# BLDCSuperBot.net
KiCad netlist of a schematic drawn in Altium Designer
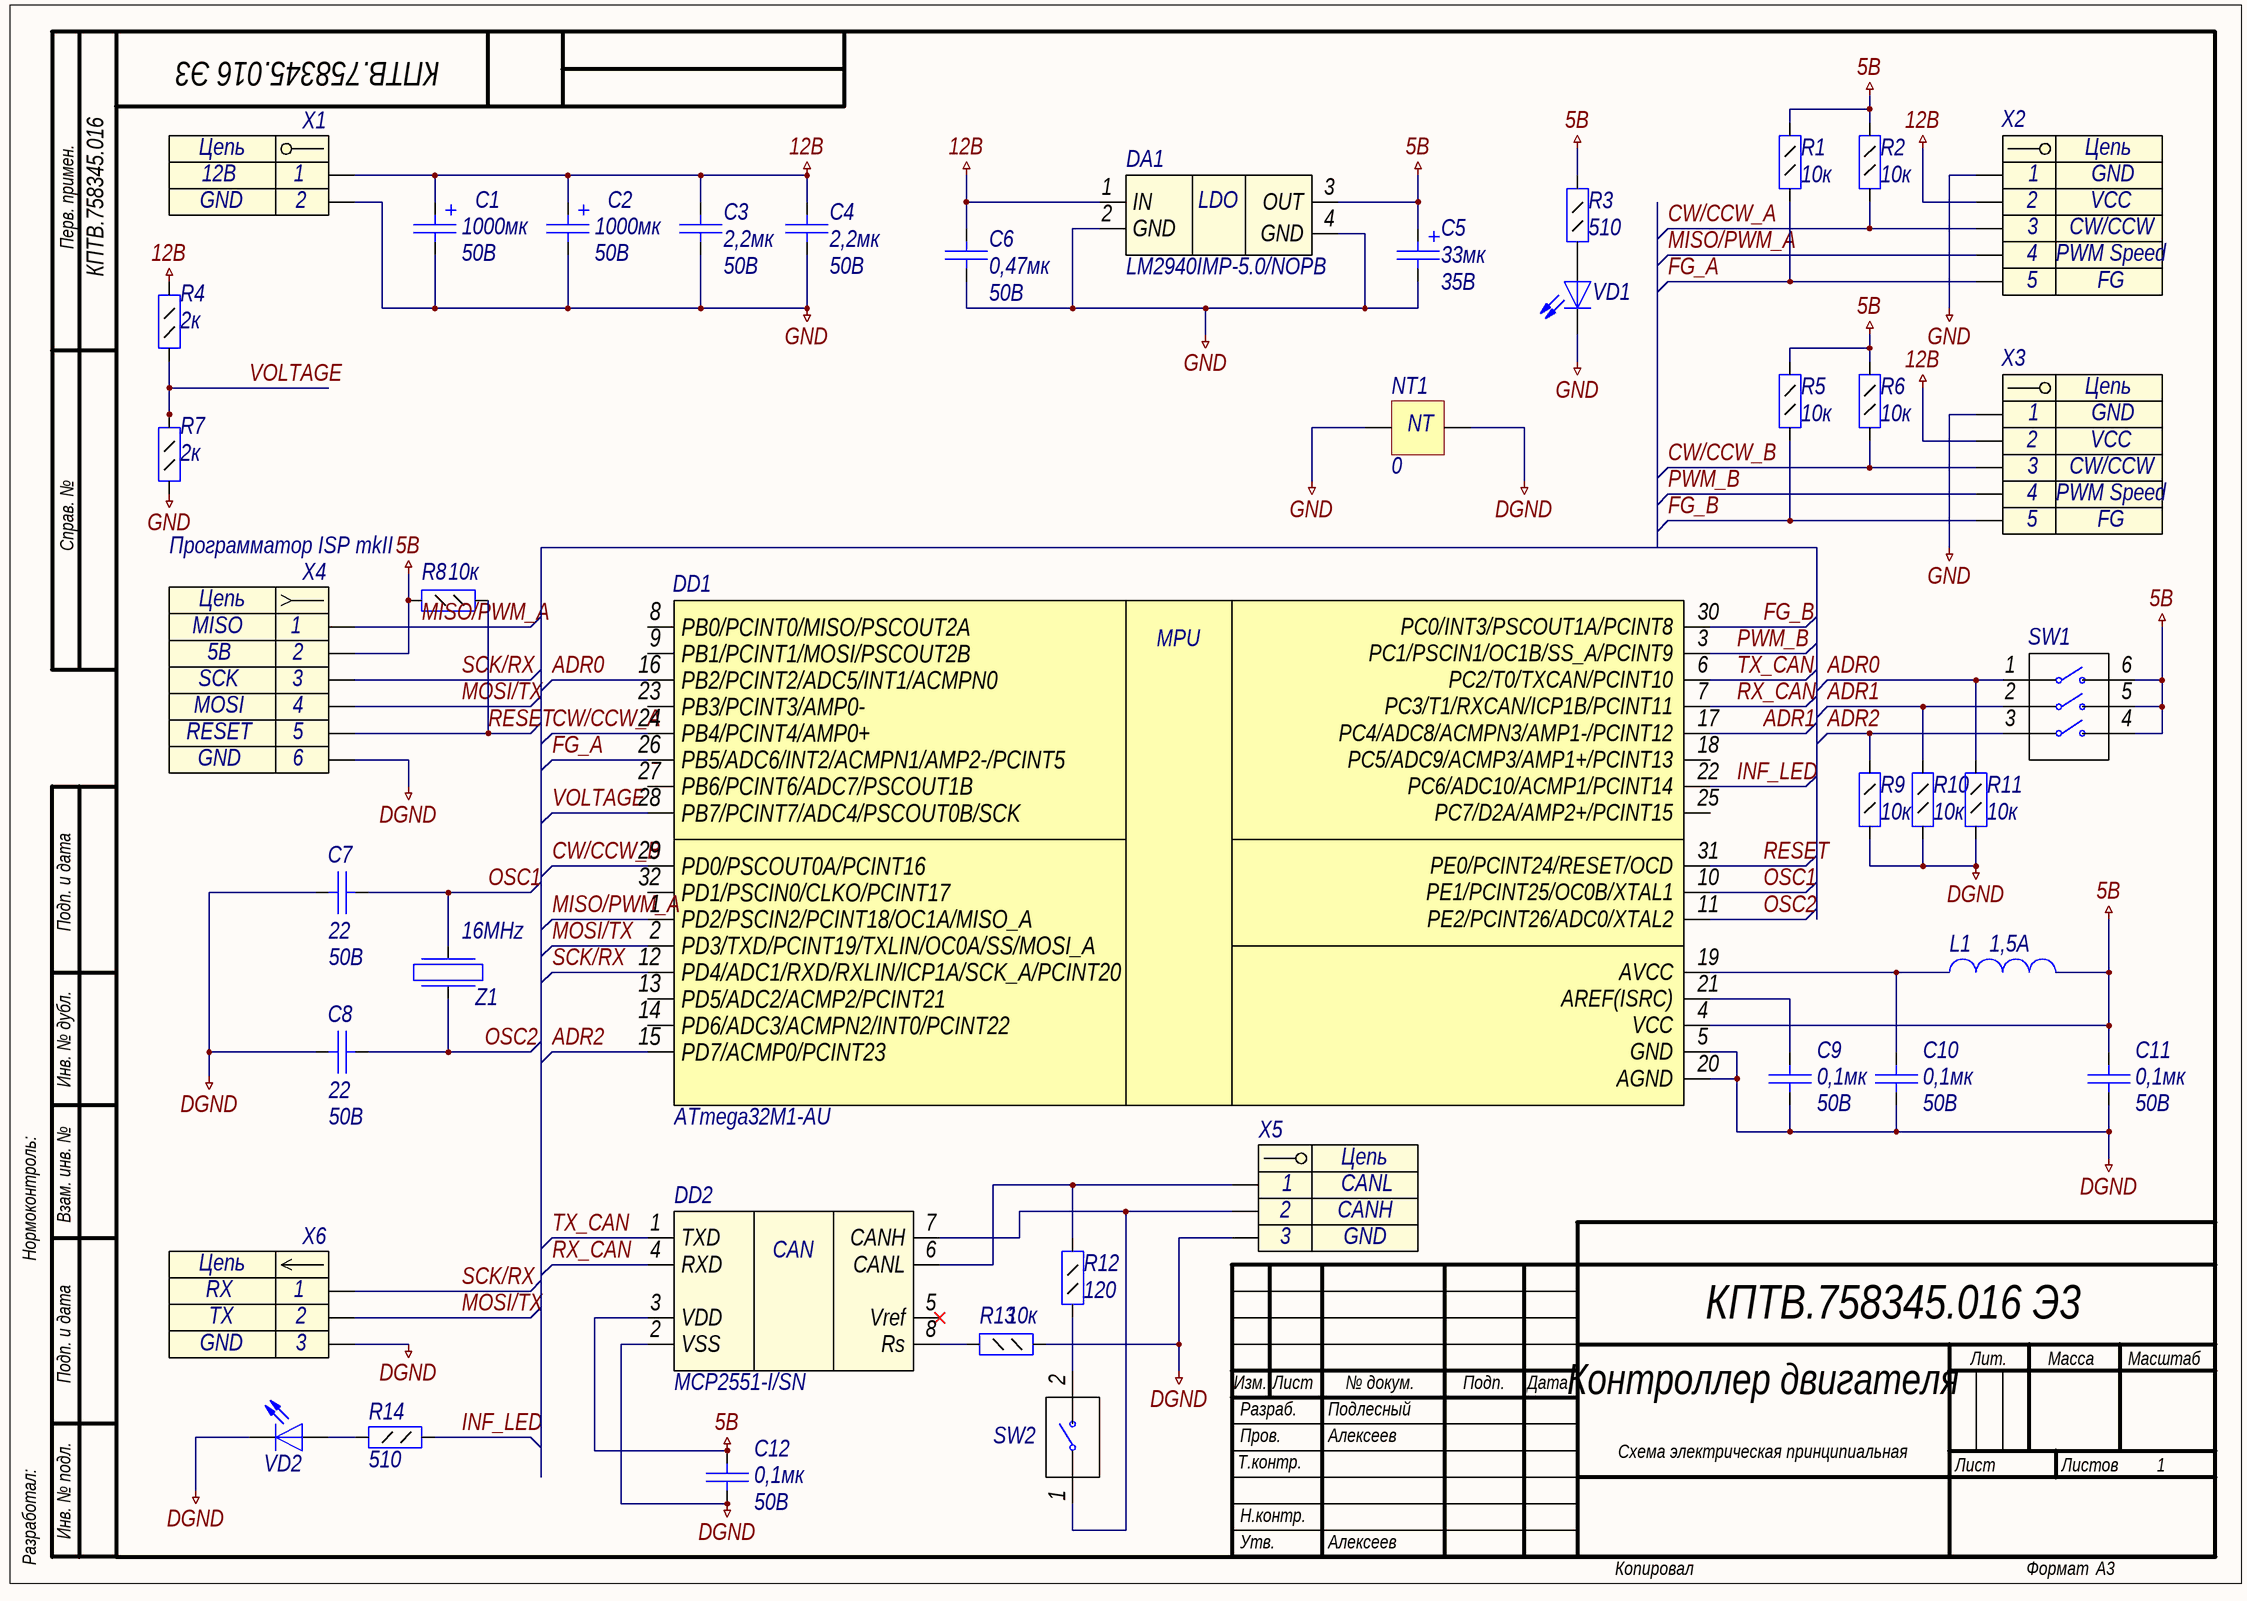
[diagram p0: BLDCSuperBot.schdoc]

(export (version "E")
  (design (tool "Eeschema 10.0.6"))
  (components
    (comp (ref "C1")
      (value "1000мк")
      (footprint "K50-35(13X25)_V")
      (description "Конденсатор полярный")
      (fields
        (field (name "VOLTAGE") "50В")
        (field (name "PART NUMBER") "TKR102M1HJ21")
        (field (name "Comment") "Capacitor_pol")
      )
      (libsource (lib "MOP44") (part "Capacitor_pol"))
    )
    (comp (ref "C2")
      (value "1000мк")
      (footprint "K50-35(13X25)_V")
      (description "Конденсатор полярный")
      (fields
        (field (name "VOLTAGE") "50В")
        (field (name "PART NUMBER") "TKR102M1HJ21")
        (field (name "Comment") "Capacitor_pol")
      )
      (libsource (lib "MOP44") (part "Capacitor_pol"))
    )
    (comp (ref "C3")
      (value "2,2мк")
      (footprint "C1206")
      (description "Конденсатор")
      (fields
        (field (name "VOLTAGE") "50В")
        (field (name "PART NUMBER") "GRM31CR71H225KA88**L")
        (field (name "Comment") "Capacitor")
      )
      (libsource (lib "MOP44") (part "Capacitor"))
    )
    (comp (ref "C4")
      (value "2,2мк")
      (footprint "C1206")
      (description "Конденсатор")
      (fields
        (field (name "VOLTAGE") "50В")
        (field (name "PART NUMBER") "GRM31CR71H225KA88**L")
        (field (name "Comment") "Capacitor")
      )
      (libsource (lib "MOP44") (part "Capacitor"))
    )
    (comp (ref "C5")
      (value "33мк")
      (footprint "TANTAL CASE D")
      (description "Конденсатор полярный")
      (fields
        (field (name "VOLTAGE") "35В")
        (field (name "PART NUMBER") "TAJD336K035RNJ")
        (field (name "Comment") "Capacitor_pol")
      )
      (libsource (lib "MOP44") (part "Capacitor_pol"))
    )
    (comp (ref "C6")
      (value "0,47мк")
      (footprint "C0805")
      (description "Конденсатор")
      (fields
        (field (name "VOLTAGE") "50B")
        (field (name "PART NUMBER") "GRM219R71C474K")
        (field (name "Comment") "Capacitor")
      )
      (libsource (lib "MOP44") (part "Capacitor"))
    )
    (comp (ref "C7")
      (value "22")
      (footprint "C0805")
      (description "Конденсатор")
      (fields
        (field (name "VOLTAGE") "50В")
        (field (name "PART NUMBER") "GRM21A5C2E220JW01D")
        (field (name "Comment") "Capacitor")
      )
      (libsource (lib "MOP44") (part "Capacitor"))
    )
    (comp (ref "C8")
      (value "22")
      (footprint "C0805")
      (description "Конденсатор")
      (fields
        (field (name "VOLTAGE") "50В")
        (field (name "PART NUMBER") "GRM21A5C2E220JW01D")
        (field (name "Comment") "Capacitor")
      )
      (libsource (lib "MOP44") (part "Capacitor"))
    )
    (comp (ref "C9")
      (value "0,1мк")
      (footprint "C0805")
      (description "Конденсатор")
      (fields
        (field (name "VOLTAGE") "50В")
        (field (name "PART NUMBER") "GRM21BR71H104KA01L ")
        (field (name "Comment") "Capacitor")
      )
      (libsource (lib "MOP44") (part "Capacitor"))
    )
    (comp (ref "C10")
      (value "0,1мк")
      (footprint "C0805")
      (description "Конденсатор")
      (fields
        (field (name "VOLTAGE") "50В")
        (field (name "PART NUMBER") "GRM21BR71H104KA01L ")
        (field (name "Comment") "Capacitor")
      )
      (libsource (lib "MOP44") (part "Capacitor"))
    )
    (comp (ref "C11")
      (value "0,1мк")
      (footprint "C0805")
      (description "Конденсатор")
      (fields
        (field (name "VOLTAGE") "50В")
        (field (name "PART NUMBER") "GRM21BR71H104KA01L ")
        (field (name "Comment") "Capacitor")
      )
      (libsource (lib "MOP44") (part "Capacitor"))
    )
    (comp (ref "C12")
      (value "0,1мк")
      (footprint "C0805")
      (description "Конденсатор")
      (fields
        (field (name "VOLTAGE") "50В")
        (field (name "PART NUMBER") "GRM21BR71H104KA01L ")
        (field (name "Comment") "Capacitor")
      )
      (libsource (lib "MOP44") (part "Capacitor"))
    )
    (comp (ref "DA1")
      (value "LM2940IMP")
      (footprint "SOT-223")
      (description "Low-Dropout Regulator for 5-V to 3.3-V Conversion")
      (fields
        (field (name "PART NUMBER") "LM2940IMP-5.0/NOPB")
        (field (name "MANUFACTURER") "Texas Instruments")
      )
      (libsource (lib "MOP44") (part "LM2940IMP"))
    )
    (comp (ref "DD1")
      (value "ATmega32M1-AU")
      (footprint "TQFP-32")
      (description "Микроконтроллер 8-Бит, AVR, 16МГц, 32КБ Flash")
      (libsource (lib "MOP44") (part "ATmega32M1-AU"))
    )
    (comp (ref "DD2")
      (value "MCP2551-I/SN")
      (footprint "SO8")
      (description "High-Speed CAN Transceiver")
      (libsource (lib "MOP44") (part "MCP2551-I/SN"))
    )
    (comp (ref "L1")
      (value "Inductor")
      (footprint "L0603")
      (description "EMI Suppression Filter")
      (fields (field (name "RATED CURRENT") "1,5A") (field (name "PART NUMBER") "BLM18PG181SN1D"))
      (libsource (lib "MOP44") (part "Inductor"))
    )
    (comp (ref "NT1") (value "0") (footprint "Pofigistor0603") (libsource (lib "MOP44") (part "Pofigistor")))
    (comp (ref "R1")
      (value "10к")
      (footprint "R0805")
      (description "Резистор")
      (fields (field (name "POWER") "0,125Вт") (field (name "Comment") "Resistor_0,125Вт"))
      (libsource (lib "") (part "Resistor_0,125Вт_1"))
    )
    (comp (ref "R2")
      (value "10к")
      (footprint "R0805")
      (description "Резистор")
      (fields (field (name "POWER") "0,125Вт") (field (name "Comment") "Resistor_0,125Вт"))
      (libsource (lib "") (part "Resistor_0,125Вт_1"))
    )
    (comp (ref "R3")
      (value "510")
      (footprint "R0805")
      (description "Резистор")
      (fields (field (name "PART NUMBER") "RC0805FR-07510RL") (field (name "POWER") "0,125Вт"))
      (libsource (lib "") (part "Resistor_0,125Вт_2"))
    )
    (comp (ref "R4")
      (value "2к")
      (footprint "R0805")
      (description "Резистор")
      (fields (field (name "PART NUMBER") "RC0805FR-072KL") (field (name "POWER") "0,125Вт"))
      (libsource (lib "") (part "Resistor_0,125Вт_2"))
    )
    (comp (ref "R5")
      (value "10к")
      (footprint "R0805")
      (description "Резистор")
      (fields (field (name "POWER") "0,125Вт") (field (name "Comment") "Resistor_0,125Вт"))
      (libsource (lib "") (part "Resistor_0,125Вт_1"))
    )
    (comp (ref "R6")
      (value "10к")
      (footprint "R0805")
      (description "Резистор")
      (fields (field (name "POWER") "0,125Вт") (field (name "Comment") "Resistor_0,125Вт"))
      (libsource (lib "") (part "Resistor_0,125Вт_1"))
    )
    (comp (ref "R7")
      (value "2к")
      (footprint "R0805")
      (description "Резистор")
      (fields (field (name "PART NUMBER") "RC0805FR-072KL") (field (name "POWER") "0,125Вт"))
      (libsource (lib "") (part "Resistor_0,125Вт_2"))
    )
    (comp (ref "R8")
      (value "10к")
      (footprint "R0805")
      (description "Резистор")
      (fields (field (name "POWER") "0,125Вт") (field (name "Comment") "Resistor_0,125Вт"))
      (libsource (lib "MOP44") (part "Resistor_0,125Вт"))
    )
    (comp (ref "R9")
      (value "10к")
      (footprint "R0805")
      (description "Резистор")
      (fields (field (name "POWER") "0,125Вт") (field (name "Comment") "Resistor_0,125Вт"))
      (libsource (lib "") (part "Resistor_0,125Вт_1"))
    )
    (comp (ref "R10")
      (value "10к")
      (footprint "R0805")
      (description "Резистор")
      (fields (field (name "POWER") "0,125Вт") (field (name "Comment") "Resistor_0,125Вт"))
      (libsource (lib "") (part "Resistor_0,125Вт_1"))
    )
    (comp (ref "R11")
      (value "10к")
      (footprint "R0805")
      (description "Резистор")
      (fields (field (name "POWER") "0,125Вт") (field (name "Comment") "Resistor_0,125Вт"))
      (libsource (lib "") (part "Resistor_0,125Вт_1"))
    )
    (comp (ref "R12")
      (value "120")
      (footprint "R0805")
      (description "Резистор")
      (fields (field (name "PART NUMBER") "RC0805FR-07120RL") (field (name "POWER") "0,125Вт"))
      (libsource (lib "") (part "Resistor_0,125Вт_2"))
    )
    (comp (ref "R13")
      (value "10к")
      (footprint "R0805")
      (description "Резистор")
      (fields (field (name "POWER") "0,125Вт") (field (name "Comment") "Resistor_0,125Вт"))
      (libsource (lib "MOP44") (part "Resistor_0,125Вт"))
    )
    (comp (ref "R14")
      (value "510")
      (footprint "R0805")
      (description "Резистор")
      (fields (field (name "PART NUMBER") "RC0805FR-07510RL") (field (name "POWER") "0,125Вт"))
      (libsource (lib "") (part "Resistor_0,125Вт_1"))
    )
    (comp (ref "SW1")
      (value "~")
      (footprint "DIP3")
      (description "DIP переключатель адреса")
      (fields (field (name "PART NUMBER") "DS1040-03RN"))
      (libsource (lib "MOP44") (part "DS1040-03"))
    )
    (comp (ref "SW2")
      (value "DS1040-01")
      (footprint "DIP1")
      (description "DIP переключатель")
      (fields (field (name "PART NUMBER") "DS1040-01RN"))
      (libsource (lib "MOP44") (part "DS1040-01"))
    )
    (comp (ref "VD1")
      (value "LED")
      (footprint "L_0805")
      (description "Светодиод")
      (fields (field (name "PART NUMBER") "KP-2012EC"))
      (libsource (lib "MOP44") (part "LED"))
    )
    (comp (ref "VD2")
      (value "LED")
      (footprint "L_0805")
      (description "Светодиод")
      (fields (field (name "PART NUMBER") "KP-2012EC"))
      (libsource (lib "MOP44") (part "LED"))
    )
    (comp (ref "X1")
      (value "Header_2_trm")
      (footprint "TERMINAL-2WAY-5MM")
      (description "Разъем - 2 конт. клеммник")
      (libsource (lib "MOP44") (part "Header_2_trm"))
    )
    (comp (ref "X2")
      (value "Header_5_trm")
      (footprint "TERMINAL-5WAY-3.5MM_")
      (description "Разъем - 5 конт. клеммник")
      (libsource (lib "MOP44") (part "Header_5_trm"))
    )
    (comp (ref "X3")
      (value "Header_5_trm")
      (footprint "TERMINAL-5WAY-3.5MM")
      (description "Разъем - 5 конт. клеммник")
      (libsource (lib "MOP44") (part "Header_5_trm"))
    )
    (comp (ref "X4")
      (value "Программатор ISP mkII")
      (footprint "PLS2-6")
      (description "Разъем - 6 конт. розетка")
      (libsource (lib "MOP44") (part "Header_6_sct"))
    )
    (comp (ref "X5")
      (value "Header_3_trm")
      (footprint "TERMINAL-3WAY-3.5MM")
      (description "Разъем - 3 конт. клеммник")
      (libsource (lib "MOP44") (part "Header_3_trm"))
    )
    (comp (ref "X6")
      (value "Header_3_plg")
      (footprint "PLS-3")
      (description "Разъем - 3 конт. вилка")
      (fields (field (name "PART NUMBER") "DS1021-1*3SF112-B"))
      (libsource (lib "MOP44") (part "Header_3_plg"))
    )
    (comp (ref "Z1")
      (value "Crystal")
      (footprint "HC-49S")
      (description "Кварцевый резонатор")
      (fields (field (name "FREQUENCE") "16MHz") (field (name "PART NUMBER") "16.000MHzHC-49US"))
      (libsource (lib "MOP44") (part "Crystal"))
    )
  )
  (nets
    (net (code "1") (name "/ADR0") (class "Default")
      (node (ref "DD1") (pin "16") (pinfunction "PB2/PCINT2/ADC5/INT1/ACMPN0_16") (pintype "passive"))
      (node (ref "R11") (pin "1") (pinfunction "1_1") (pintype "passive"))
      (node (ref "SW1") (pin "1") (pintype "passive"))
    )
    (net (code "2") (name "/ADR1") (class "Default")
      (node (ref "DD1") (pin "17") (pinfunction "PC4/ADC8/ACMPN3/AMP1-/PCINT12_17") (pintype "passive"))
      (node (ref "R10") (pin "1") (pinfunction "1_1") (pintype "passive"))
      (node (ref "SW1") (pin "2") (pintype "passive"))
    )
    (net (code "3") (name "/ADR2") (class "Default")
      (node (ref "DD1") (pin "15") (pinfunction "PD7/ACMP0/PCINT23_15") (pintype "passive"))
      (node (ref "R9") (pin "1") (pinfunction "1_1") (pintype "passive"))
      (node (ref "SW1") (pin "3") (pintype "passive"))
    )
    (net (code "4") (name "/CW{slash}CCW_A") (class "Default")
      (node (ref "DD1") (pin "24") (pinfunction "PB4/PCINT4/AMP0+_24") (pintype "passive"))
      (node (ref "R2") (pin "2") (pinfunction "2_2") (pintype "passive"))
      (node (ref "X2") (pin "3") (pinfunction "3_3") (pintype "passive"))
    )
    (net (code "5") (name "/CW{slash}CCW_B") (class "Default")
      (node (ref "DD1") (pin "29") (pinfunction "PD0/PSCOUT0A/PCINT16_29") (pintype "passive"))
      (node (ref "R6") (pin "2") (pinfunction "2_2") (pintype "passive"))
      (node (ref "X3") (pin "3") (pinfunction "3_3") (pintype "passive"))
    )
    (net (code "6") (name "/FG_A") (class "Default")
      (node (ref "DD1") (pin "26") (pinfunction "PB5/ADC6/INT2/ACMPN1/AMP2-/PCINT5_26") (pintype "passive"))
      (node (ref "R1") (pin "2") (pinfunction "2_2") (pintype "passive"))
      (node (ref "X2") (pin "5") (pinfunction "5_5") (pintype "passive"))
    )
    (net (code "7") (name "/FG_B") (class "Default")
      (node (ref "DD1") (pin "30") (pinfunction "PC0/INT3/PSCOUT1A/PCINT8_30") (pintype "passive"))
      (node (ref "R5") (pin "2") (pinfunction "2_2") (pintype "passive"))
      (node (ref "X3") (pin "5") (pinfunction "5_5") (pintype "passive"))
    )
    (net (code "8") (name "/INF_LED") (class "Default")
      (node (ref "DD1") (pin "22") (pinfunction "PC6/ADC10/ACMP1/PCINT14_22") (pintype "passive"))
      (node (ref "R14") (pin "1") (pinfunction "1_1") (pintype "passive"))
    )
    (net (code "9") (name "/MISO{slash}PWM_A") (class "Default")
      (node (ref "DD1") (pin "1") (pinfunction "PD2/PSCIN2/PCINT18/OC1A/MISO_A_1") (pintype "passive"))
      (node (ref "X2") (pin "4") (pinfunction "4_4") (pintype "passive"))
      (node (ref "X4") (pin "1") (pinfunction "1_1") (pintype "passive"))
    )
    (net (code "10") (name "/MOSI{slash}TX") (class "Default")
      (node (ref "DD1") (pin "2") (pinfunction "PD3/TXD/PCINT19/TXLIN/OC0A/SS/MOSI_A_2") (pintype "passive"))
      (node (ref "X4") (pin "4") (pinfunction "4_4") (pintype "passive"))
      (node (ref "X6") (pin "2") (pinfunction "2_2") (pintype "passive"))
    )
    (net (code "11") (name "/OSC1") (class "Default")
      (node (ref "C7") (pin "1") (pinfunction "1_1") (pintype "passive"))
      (node (ref "DD1") (pin "10") (pinfunction "PE1/PCINT25/OC0B/XTAL1_10") (pintype "passive"))
      (node (ref "Z1") (pin "2") (pinfunction "2_2") (pintype "passive"))
    )
    (net (code "12") (name "/OSC2") (class "Default")
      (node (ref "C8") (pin "1") (pinfunction "1_1") (pintype "passive"))
      (node (ref "DD1") (pin "11") (pinfunction "PE2/PCINT26/ADC0/XTAL2_11") (pintype "passive"))
      (node (ref "Z1") (pin "1") (pinfunction "1_1") (pintype "passive"))
    )
    (net (code "13") (name "/PWM_B") (class "Default")
      (node (ref "DD1") (pin "3") (pinfunction "PC1/PSCIN1/OC1B/SS_A/PCINT9_3") (pintype "passive"))
      (node (ref "X3") (pin "4") (pinfunction "4_4") (pintype "passive"))
    )
    (net (code "14") (name "/RESET") (class "Default")
      (node (ref "DD1") (pin "31") (pinfunction "PE0/PCINT24/RESET/OCD_31") (pintype "passive"))
      (node (ref "R8") (pin "1") (pinfunction "1_1") (pintype "passive"))
      (node (ref "X4") (pin "5") (pinfunction "5_5") (pintype "passive"))
    )
    (net (code "15") (name "/RX_CAN") (class "Default")
      (node (ref "DD1") (pin "7") (pinfunction "PC3/T1/RXCAN/ICP1B/PCINT11_7") (pintype "passive"))
      (node (ref "DD2") (pin "4") (pinfunction "RXD_4") (pintype "power_in"))
    )
    (net (code "16") (name "/SCK{slash}RX") (class "Default")
      (node (ref "DD1") (pin "12") (pinfunction "PD4/ADC1/RXD/RXLIN/ICP1A/SCK_A/PCINT20_12") (pintype "passive"))
      (node (ref "X4") (pin "3") (pinfunction "3_3") (pintype "passive"))
      (node (ref "X6") (pin "1") (pinfunction "1_1") (pintype "passive"))
    )
    (net (code "17") (name "/TX_CAN") (class "Default")
      (node (ref "DD1") (pin "6") (pinfunction "PC2/T0/TXCAN/PCINT10_6") (pintype "passive"))
      (node (ref "DD2") (pin "1") (pinfunction "TXD_1") (pintype "power_in"))
    )
    (net (code "18") (name "/VOLTAGE") (class "Default")
      (node (ref "DD1") (pin "28") (pinfunction "PB7/PCINT7/ADC4/PSCOUT0B/SCK_28") (pintype "passive"))
      (node (ref "R4") (pin "1") (pinfunction "1_1") (pintype "passive"))
      (node (ref "R7") (pin "2") (pinfunction "2_2") (pintype "passive"))
    )
    (net (code "19") (name "5B") (class "Default")
      (node (ref "C11") (pin "2") (pinfunction "2_2") (pintype "passive"))
      (node (ref "C12") (pin "2") (pinfunction "2_2") (pintype "passive"))
      (node (ref "C5") (pin "1") (pinfunction "1_1") (pintype "passive"))
      (node (ref "DA1") (pin "3") (pinfunction "OUT_3") (pintype "power_in"))
      (node (ref "DD1") (pin "4") (pinfunction "VCC_4") (pintype "passive"))
      (node (ref "DD2") (pin "3") (pinfunction "VDD_3") (pintype "power_in"))
      (node (ref "L1") (pin "2") (pinfunction "2_2") (pintype "passive"))
      (node (ref "R1") (pin "1") (pinfunction "1_1") (pintype "passive"))
      (node (ref "R2") (pin "1") (pinfunction "1_1") (pintype "passive"))
      (node (ref "R3") (pin "2") (pinfunction "2_2") (pintype "passive"))
      (node (ref "R5") (pin "1") (pinfunction "1_1") (pintype "passive"))
      (node (ref "R6") (pin "1") (pinfunction "1_1") (pintype "passive"))
      (node (ref "R8") (pin "2") (pinfunction "2_2") (pintype "passive"))
      (node (ref "SW1") (pin "4") (pintype "passive"))
      (node (ref "SW1") (pin "5") (pintype "passive"))
      (node (ref "SW1") (pin "6") (pintype "passive"))
      (node (ref "X4") (pin "2") (pinfunction "2_2") (pintype "passive"))
    )
    (net (code "20") (name "12B") (class "Default")
      (node (ref "C1") (pin "1") (pinfunction "1_1") (pintype "passive"))
      (node (ref "C2") (pin "1") (pinfunction "1_1") (pintype "passive"))
      (node (ref "C3") (pin "2") (pinfunction "2_2") (pintype "passive"))
      (node (ref "C4") (pin "2") (pinfunction "2_2") (pintype "passive"))
      (node (ref "C6") (pin "2") (pinfunction "2_2") (pintype "passive"))
      (node (ref "DA1") (pin "1") (pinfunction "IN_1") (pintype "power_in"))
      (node (ref "R4") (pin "2") (pinfunction "2_2") (pintype "passive"))
      (node (ref "X1") (pin "1") (pinfunction "1_1") (pintype "passive"))
      (node (ref "X2") (pin "2") (pinfunction "2_2") (pintype "passive"))
      (node (ref "X3") (pin "2") (pinfunction "2_2") (pintype "passive"))
    )
    (net (code "21") (name "DGND") (class "Default")
      (node (ref "C10") (pin "1") (pinfunction "1_1") (pintype "passive"))
      (node (ref "C11") (pin "1") (pinfunction "1_1") (pintype "passive"))
      (node (ref "C12") (pin "1") (pinfunction "1_1") (pintype "passive"))
      (node (ref "C7") (pin "2") (pinfunction "2_2") (pintype "passive"))
      (node (ref "C8") (pin "2") (pinfunction "2_2") (pintype "passive"))
      (node (ref "C9") (pin "1") (pinfunction "1_1") (pintype "passive"))
      (node (ref "DD1") (pin "20") (pinfunction "AGND_20") (pintype "passive"))
      (node (ref "DD1") (pin "5") (pinfunction "GND_5") (pintype "passive"))
      (node (ref "DD2") (pin "2") (pinfunction "VSS_2") (pintype "power_in"))
      (node (ref "NT1") (pin "2") (pinfunction "2_2") (pintype "passive"))
      (node (ref "R10") (pin "2") (pinfunction "2_2") (pintype "passive"))
      (node (ref "R11") (pin "2") (pinfunction "2_2") (pintype "passive"))
      (node (ref "R13") (pin "1") (pinfunction "1_1") (pintype "passive"))
      (node (ref "R9") (pin "2") (pinfunction "2_2") (pintype "passive"))
      (node (ref "VD2") (pin "1") (pinfunction "K_1") (pintype "passive"))
      (node (ref "X4") (pin "6") (pinfunction "6_6") (pintype "passive"))
      (node (ref "X5") (pin "3") (pinfunction "3_3") (pintype "passive"))
      (node (ref "X6") (pin "3") (pinfunction "3_3") (pintype "passive"))
    )
    (net (code "22") (name "GND") (class "Default")
      (node (ref "C1") (pin "2") (pinfunction "2_2") (pintype "passive"))
      (node (ref "C2") (pin "2") (pinfunction "2_2") (pintype "passive"))
      (node (ref "C3") (pin "1") (pinfunction "1_1") (pintype "passive"))
      (node (ref "C4") (pin "1") (pinfunction "1_1") (pintype "passive"))
      (node (ref "C5") (pin "2") (pinfunction "2_2") (pintype "passive"))
      (node (ref "C6") (pin "1") (pinfunction "1_1") (pintype "passive"))
      (node (ref "DA1") (pin "2") (pinfunction "GND_2") (pintype "power_in"))
      (node (ref "DA1") (pin "4") (pinfunction "GND_4") (pintype "power_in"))
      (node (ref "NT1") (pin "1") (pinfunction "1_1") (pintype "passive"))
      (node (ref "R7") (pin "1") (pinfunction "1_1") (pintype "passive"))
      (node (ref "VD1") (pin "1") (pinfunction "K_1") (pintype "passive"))
      (node (ref "X1") (pin "2") (pinfunction "2_2") (pintype "passive"))
      (node (ref "X2") (pin "1") (pinfunction "1_1") (pintype "passive"))
      (node (ref "X3") (pin "1") (pinfunction "1_1") (pintype "passive"))
    )
    (net (code "23") (name "Net-(DD1-AREF(ISRC))") (class "Default")
      (node (ref "C9") (pin "2") (pinfunction "2_2") (pintype "passive"))
      (node (ref "DD1") (pin "21") (pinfunction "AREF(ISRC)_21") (pintype "passive"))
    )
    (net (code "24") (name "Net-(DD1-AVCC)") (class "Default")
      (node (ref "C10") (pin "2") (pinfunction "2_2") (pintype "passive"))
      (node (ref "DD1") (pin "19") (pinfunction "AVCC_19") (pintype "passive"))
      (node (ref "L1") (pin "1") (pinfunction "1_1") (pintype "passive"))
    )
    (net (code "25") (name "Net-(DD2-CANH)") (class "Default")
      (node (ref "DD2") (pin "7") (pinfunction "CANH_7") (pintype "power_in"))
      (node (ref "SW2") (pin "1") (pintype "passive"))
      (node (ref "X5") (pin "2") (pinfunction "2_2") (pintype "passive"))
    )
    (net (code "26") (name "Net-(DD2-CANL)") (class "Default")
      (node (ref "DD2") (pin "6") (pinfunction "CANL_6") (pintype "power_in"))
      (node (ref "R12") (pin "2") (pinfunction "2_2") (pintype "passive"))
      (node (ref "X5") (pin "1") (pinfunction "1_1") (pintype "passive"))
    )
    (net (code "27") (name "Net-(DD2-Rs)") (class "Default")
      (node (ref "DD2") (pin "8") (pinfunction "Rs_8") (pintype "power_in"))
      (node (ref "R13") (pin "2") (pinfunction "2_2") (pintype "passive"))
    )
    (net (code "28") (name "Net-(R12-Pad1)") (class "Default")
      (node (ref "R12") (pin "1") (pinfunction "1_1") (pintype "passive"))
      (node (ref "SW2") (pin "2") (pintype "passive"))
    )
    (net (code "29") (name "Net-(VD1-A)") (class "Default")
      (node (ref "R3") (pin "1") (pinfunction "1_1") (pintype "passive"))
      (node (ref "VD1") (pin "2") (pinfunction "A_2") (pintype "passive"))
    )
    (net (code "30") (name "Net-(VD2-A)") (class "Default")
      (node (ref "R14") (pin "2") (pinfunction "2_2") (pintype "passive"))
      (node (ref "VD2") (pin "2") (pinfunction "A_2") (pintype "passive"))
    )
    (net (code "31") (name "unconnected-(DD1-PB0{slash}PCINT0{slash}MISO{slash}PSCOUT2A-Pad8)") (class "Default")
      (node (ref "DD1") (pin "8") (pinfunction "PB0/PCINT0/MISO/PSCOUT2A_8") (pintype "passive"))
    )
    (net (code "32") (name "unconnected-(DD1-PB1{slash}PCINT1{slash}MOSI{slash}PSCOUT2B-Pad9)") (class "Default")
      (node (ref "DD1") (pin "9") (pinfunction "PB1/PCINT1/MOSI/PSCOUT2B_9") (pintype "passive"))
    )
    (net (code "33") (name "unconnected-(DD1-PB3{slash}PCINT3{slash}AMP0--Pad23)") (class "Default")
      (node (ref "DD1") (pin "23") (pinfunction "PB3/PCINT3/AMP0-_23") (pintype "passive"))
    )
    (net (code "34") (name "unconnected-(DD1-PB6{slash}PCINT6{slash}ADC7{slash}PSCOUT1B-Pad27)") (class "Default")
      (node (ref "DD1") (pin "27") (pinfunction "PB6/PCINT6/ADC7/PSCOUT1B_27") (pintype "passive"))
    )
    (net (code "35") (name "unconnected-(DD1-PC5{slash}ADC9{slash}ACMP3{slash}AMP1+{slash}PCINT13-Pad18)") (class "Default")
      (node (ref "DD1") (pin "18") (pinfunction "PC5/ADC9/ACMP3/AMP1+/PCINT13_18") (pintype "passive"))
    )
    (net (code "36") (name "unconnected-(DD1-PC7{slash}D2A{slash}AMP2+{slash}PCINT15-Pad25)") (class "Default")
      (node (ref "DD1") (pin "25") (pinfunction "PC7/D2A/AMP2+/PCINT15_25") (pintype "passive"))
    )
    (net (code "37") (name "unconnected-(DD1-PD1{slash}PSCIN0{slash}CLKO{slash}PCINT17-Pad32)") (class "Default")
      (node (ref "DD1") (pin "32") (pinfunction "PD1/PSCIN0/CLKO/PCINT17_32") (pintype "passive"))
    )
    (net (code "38") (name "unconnected-(DD1-PD5{slash}ADC2{slash}ACMP2{slash}PCINT21-Pad13)") (class "Default")
      (node (ref "DD1") (pin "13") (pinfunction "PD5/ADC2/ACMP2/PCINT21_13") (pintype "passive"))
    )
    (net (code "39") (name "unconnected-(DD1-PD6{slash}ADC3{slash}ACMPN2{slash}INT0{slash}PCINT22-Pad14)") (class "Default")
      (node (ref "DD1") (pin "14") (pinfunction "PD6/ADC3/ACMPN2/INT0/PCINT22_14") (pintype "passive"))
    )
    (net (code "40") (name "unconnected-(DD2-Vref-Pad5)") (class "Default")
      (node (ref "DD2") (pin "5") (pinfunction "Vref_5") (pintype "power_in+no_connect"))
    )
  )
)
